# key.net
KiCad netlist of a schematic drawn in Altium Designer
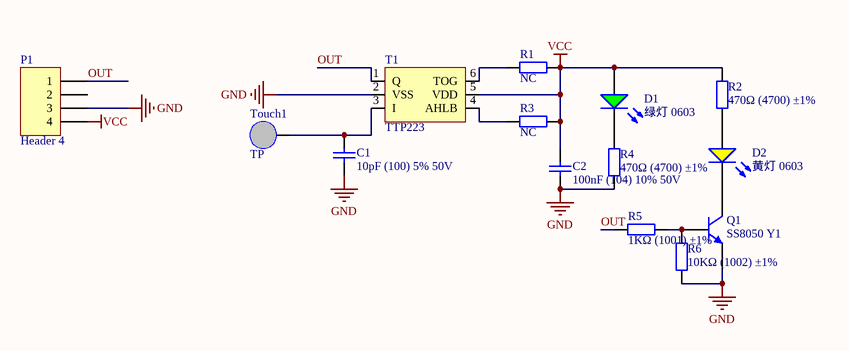
[diagram p0: key.SchDoc]

(export (version "E")
  (design (tool "Eeschema 10.0.6"))
  (components
    (comp (ref "C1")
      (value "10pF (100) 5% 50V")
      (footprint "0603_C")
      (description "贴片电容")
      (libsource (lib "Miscellaneous Devices LC") (part "0603 10pF (100) 5% 50V"))
    )
    (comp (ref "C2")
      (value "100nF (104) 10% 50V")
      (footprint "0603_C")
      (description "贴片电容")
      (libsource (lib "Miscellaneous Devices LC") (part "0603 100nF (104) 10% 50V"))
    )
    (comp (ref "D1")
      (value "绿灯 0603")
      (footprint "0603_LED_S1")
      (description "发光二极管")
      (libsource (lib "Miscellaneous Devices LC") (part "0603 绿灯"))
    )
    (comp (ref "D2")
      (value "黄灯 0603")
      (footprint "0603_LED_S1")
      (description "发光二极管")
      (libsource (lib "Miscellaneous Devices LC") (part "0603 黄灯"))
    )
    (comp (ref "P1")
      (value "Header 4")
      (footprint "FPC1.0-2H-WS-4P")
      (description "Header, 4-Pin")
      (fields (field (name "PUBLISHER") "Altium Limited"))
      (libsource (lib "Miscellaneous Connectors") (part "Header 4"))
    )
    (comp (ref "Q1")
      (value "SS8050 Y1")
      (footprint "SOT-23(SOT-23-3)")
      (description "三极管")
      (libsource (lib "Miscellaneous Devices LC") (part "SOT-23 SS8050 Y1"))
    )
    (comp (ref "R1")
      (value "NC")
      (footprint "0603_R")
      (description "贴片电阻")
      (libsource (lib "Miscellaneous Devices LC") (part "0603 10KΩ (1002) 1%"))
    )
    (comp (ref "R2")
      (value "470Ω (4700) ±1%")
      (footprint "0603_R")
      (description "贴片电阻")
      (libsource (lib "Miscellaneous Devices LC") (part "0603 470Ω (4700) 1%"))
    )
    (comp (ref "R3")
      (value "NC")
      (footprint "0603_R")
      (description "贴片电阻")
      (libsource (lib "Miscellaneous Devices LC") (part "0603 10KΩ (1002) 1%"))
    )
    (comp (ref "R4")
      (value "470Ω (4700) ±1%")
      (footprint "0603_R")
      (description "贴片电阻")
      (libsource (lib "Miscellaneous Devices LC") (part "0603 470Ω (4700) 1%"))
    )
    (comp (ref "R5")
      (value "1KΩ (1001) ±1%")
      (footprint "0603_R")
      (description "贴片电阻")
      (libsource (lib "Miscellaneous Devices LC") (part "0603 1KΩ (1001) 1%"))
    )
    (comp (ref "R6")
      (value "10KΩ (1002) ±1%")
      (footprint "0603_R")
      (description "贴片电阻")
      (libsource (lib "") (part "0603 10KΩ (1002) 1%_1"))
    )
    (comp (ref "T1") (value "TTP223") (footprint "SOT-23-6") (libsource (lib "mylib") (part "TTP223")))
    (comp (ref "Touch1") (value "TP") (footprint "TP") (libsource (lib "mylib") (part "TP")))
  )
  (nets
    (net (code "1") (name "/OUT") (class "Default")
      (node (ref "P1") (pin "1") (pinfunction "1_1") (pintype "passive"))
      (node (ref "R5") (pin "1") (pinfunction "1_1") (pintype "passive"))
      (node (ref "T1") (pin "1") (pinfunction "Q_1") (pintype "passive"))
    )
    (net (code "2") (name "GND") (class "Default")
      (node (ref "C1") (pin "1") (pinfunction "1_1") (pintype "passive"))
      (node (ref "C2") (pin "1") (pinfunction "1_1") (pintype "passive"))
      (node (ref "P1") (pin "3") (pinfunction "3_3") (pintype "passive"))
      (node (ref "Q1") (pin "2") (pinfunction "E_2") (pintype "passive"))
      (node (ref "R4") (pin "1") (pinfunction "1_1") (pintype "passive"))
      (node (ref "R6") (pin "1") (pinfunction "1_1") (pintype "passive"))
      (node (ref "T1") (pin "2") (pinfunction "VSS_2") (pintype "passive"))
    )
    (net (code "3") (name "Net-(D1-PadK)") (class "Default")
      (node (ref "D1") (pin "K") (pinfunction "K_K") (pintype "passive"))
      (node (ref "R4") (pin "2") (pinfunction "2_2") (pintype "passive"))
    )
    (net (code "4") (name "Net-(D2-PadA)") (class "Default")
      (node (ref "D2") (pin "A") (pinfunction "A_A") (pintype "passive"))
      (node (ref "R2") (pin "1") (pinfunction "1_1") (pintype "passive"))
    )
    (net (code "5") (name "Net-(Q1-B)") (class "Default")
      (node (ref "Q1") (pin "1") (pinfunction "B_1") (pintype "passive"))
      (node (ref "R5") (pin "2") (pinfunction "2_2") (pintype "passive"))
      (node (ref "R6") (pin "2") (pinfunction "2_2") (pintype "passive"))
    )
    (net (code "6") (name "Net-(Q1-C)") (class "Default")
      (node (ref "D2") (pin "K") (pinfunction "K_K") (pintype "passive"))
      (node (ref "Q1") (pin "3") (pinfunction "C_3") (pintype "passive"))
    )
    (net (code "7") (name "Net-(T1-AHLB)") (class "Default")
      (node (ref "R3") (pin "1") (pinfunction "1_1") (pintype "passive"))
      (node (ref "T1") (pin "4") (pinfunction "AHLB_4") (pintype "passive"))
    )
    (net (code "8") (name "Net-(T1-I)") (class "Default")
      (node (ref "C1") (pin "2") (pinfunction "2_2") (pintype "passive"))
      (node (ref "T1") (pin "3") (pinfunction "I_3") (pintype "passive"))
      (node (ref "Touch1") (pin "1") (pinfunction "1_1") (pintype "passive"))
    )
    (net (code "9") (name "Net-(T1-TOG)") (class "Default")
      (node (ref "R1") (pin "1") (pinfunction "1_1") (pintype "passive"))
      (node (ref "T1") (pin "6") (pinfunction "TOG_6") (pintype "passive"))
    )
    (net (code "10") (name "VCC") (class "Default")
      (node (ref "C2") (pin "2") (pinfunction "2_2") (pintype "passive"))
      (node (ref "D1") (pin "A") (pinfunction "A_A") (pintype "passive"))
      (node (ref "P1") (pin "4") (pinfunction "4_4") (pintype "passive"))
      (node (ref "R1") (pin "2") (pinfunction "2_2") (pintype "passive"))
      (node (ref "R2") (pin "2") (pinfunction "2_2") (pintype "passive"))
      (node (ref "R3") (pin "2") (pinfunction "2_2") (pintype "passive"))
      (node (ref "T1") (pin "5") (pinfunction "VDD_5") (pintype "passive"))
    )
    (net (code "11") (name "unconnected-(P1-Pad2)") (class "Default")
      (node (ref "P1") (pin "2") (pinfunction "2_2") (pintype "passive"))
    )
  )
)
